# project_alarm.net
KiCad netlist of a schematic drawn in EAGLE
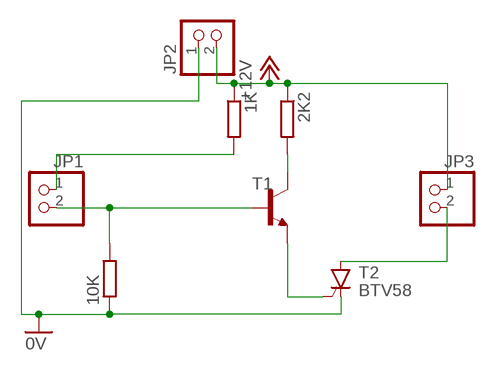
[diagram p0: schematic, sheet 1]

(export (version "E")
  (design (tool "Eeschema 10.0.6"))
  (components
    (comp (ref "1K")
      (value "R-EU_0207/15")
      (footprint "eagle-import:0207_15")
      (libsource (lib "eagle-import") (part "R-EU_0207/15"))
    )
    (comp (ref "2K2")
      (value "R-EU_0207/15")
      (footprint "eagle-import:0207_15")
      (libsource (lib "eagle-import") (part "R-EU_0207/15"))
    )
    (comp (ref "10K")
      (value "R-EU_0207/15")
      (footprint "eagle-import:0207_15")
      (libsource (lib "eagle-import") (part "R-EU_0207/15"))
    )
    (comp (ref "JP1")
      (value "PINHD-1X2")
      (footprint "eagle-import:1X02")
      (libsource (lib "eagle-import") (part "PINHD-1X2"))
    )
    (comp (ref "JP2")
      (value "PINHD-1X2")
      (footprint "eagle-import:1X02")
      (libsource (lib "eagle-import") (part "PINHD-1X2"))
    )
    (comp (ref "JP3")
      (value "PINHD-1X2")
      (footprint "eagle-import:1X02")
      (libsource (lib "eagle-import") (part "PINHD-1X2"))
    )
    (comp (ref "T1")
      (value "BC107A-NPN-TO18-EBC")
      (footprint "eagle-import:TO18")
      (libsource (lib "eagle-import") (part "-NPN-TO18-EBCBC107A"))
    )
    (comp (ref "T2")
      (value "BTV58")
      (footprint "eagle-import:TO220CS")
      (libsource (lib "eagle-import") (part "BTV58"))
    )
  )
  (nets
    (net (code "1") (name "+12V") (class "Default")
      (node (ref "1K") (pin "1") (pinfunction "1_1") (pintype "passive"))
      (node (ref "2K2") (pin "1") (pinfunction "1_1") (pintype "passive"))
      (node (ref "JP2") (pin "2") (pinfunction "2_2") (pintype "passive"))
      (node (ref "JP3") (pin "1") (pinfunction "1_1") (pintype "passive"))
    )
    (net (code "2") (name "0V") (class "Default")
      (node (ref "10K") (pin "1") (pinfunction "1_1") (pintype "passive"))
      (node (ref "JP2") (pin "1") (pinfunction "1_1") (pintype "passive"))
      (node (ref "T2") (pin "C") (pinfunction "C_C") (pintype "passive"))
    )
    (net (code "3") (name "Net-(1K-Pad2)") (class "Default")
      (node (ref "1K") (pin "2") (pinfunction "2_2") (pintype "passive"))
      (node (ref "JP1") (pin "1") (pinfunction "1_1") (pintype "passive"))
    )
    (net (code "4") (name "Net-(JP3-Pad2)") (class "Default")
      (node (ref "JP3") (pin "2") (pinfunction "2_2") (pintype "passive"))
      (node (ref "T2") (pin "A") (pinfunction "A_A") (pintype "passive"))
    )
    (net (code "5") (name "Net-(T1-B)") (class "Default")
      (node (ref "10K") (pin "2") (pinfunction "2_2") (pintype "passive"))
      (node (ref "JP1") (pin "2") (pinfunction "2_2") (pintype "passive"))
      (node (ref "T1") (pin "2") (pinfunction "B_2") (pintype "passive"))
    )
    (net (code "6") (name "Net-(T1-C)") (class "Default")
      (node (ref "2K2") (pin "2") (pinfunction "2_2") (pintype "passive"))
      (node (ref "T1") (pin "3") (pinfunction "C_3") (pintype "passive"))
    )
    (net (code "7") (name "Net-(T1-E)") (class "Default")
      (node (ref "T1") (pin "1") (pinfunction "E_1") (pintype "passive"))
      (node (ref "T2") (pin "G") (pinfunction "G_G") (pintype "passive"))
    )
  )
)
